# 3_6_1--esp32_-_0105.net
KiCad netlist of a schematic drawn in EasyEDA Pro
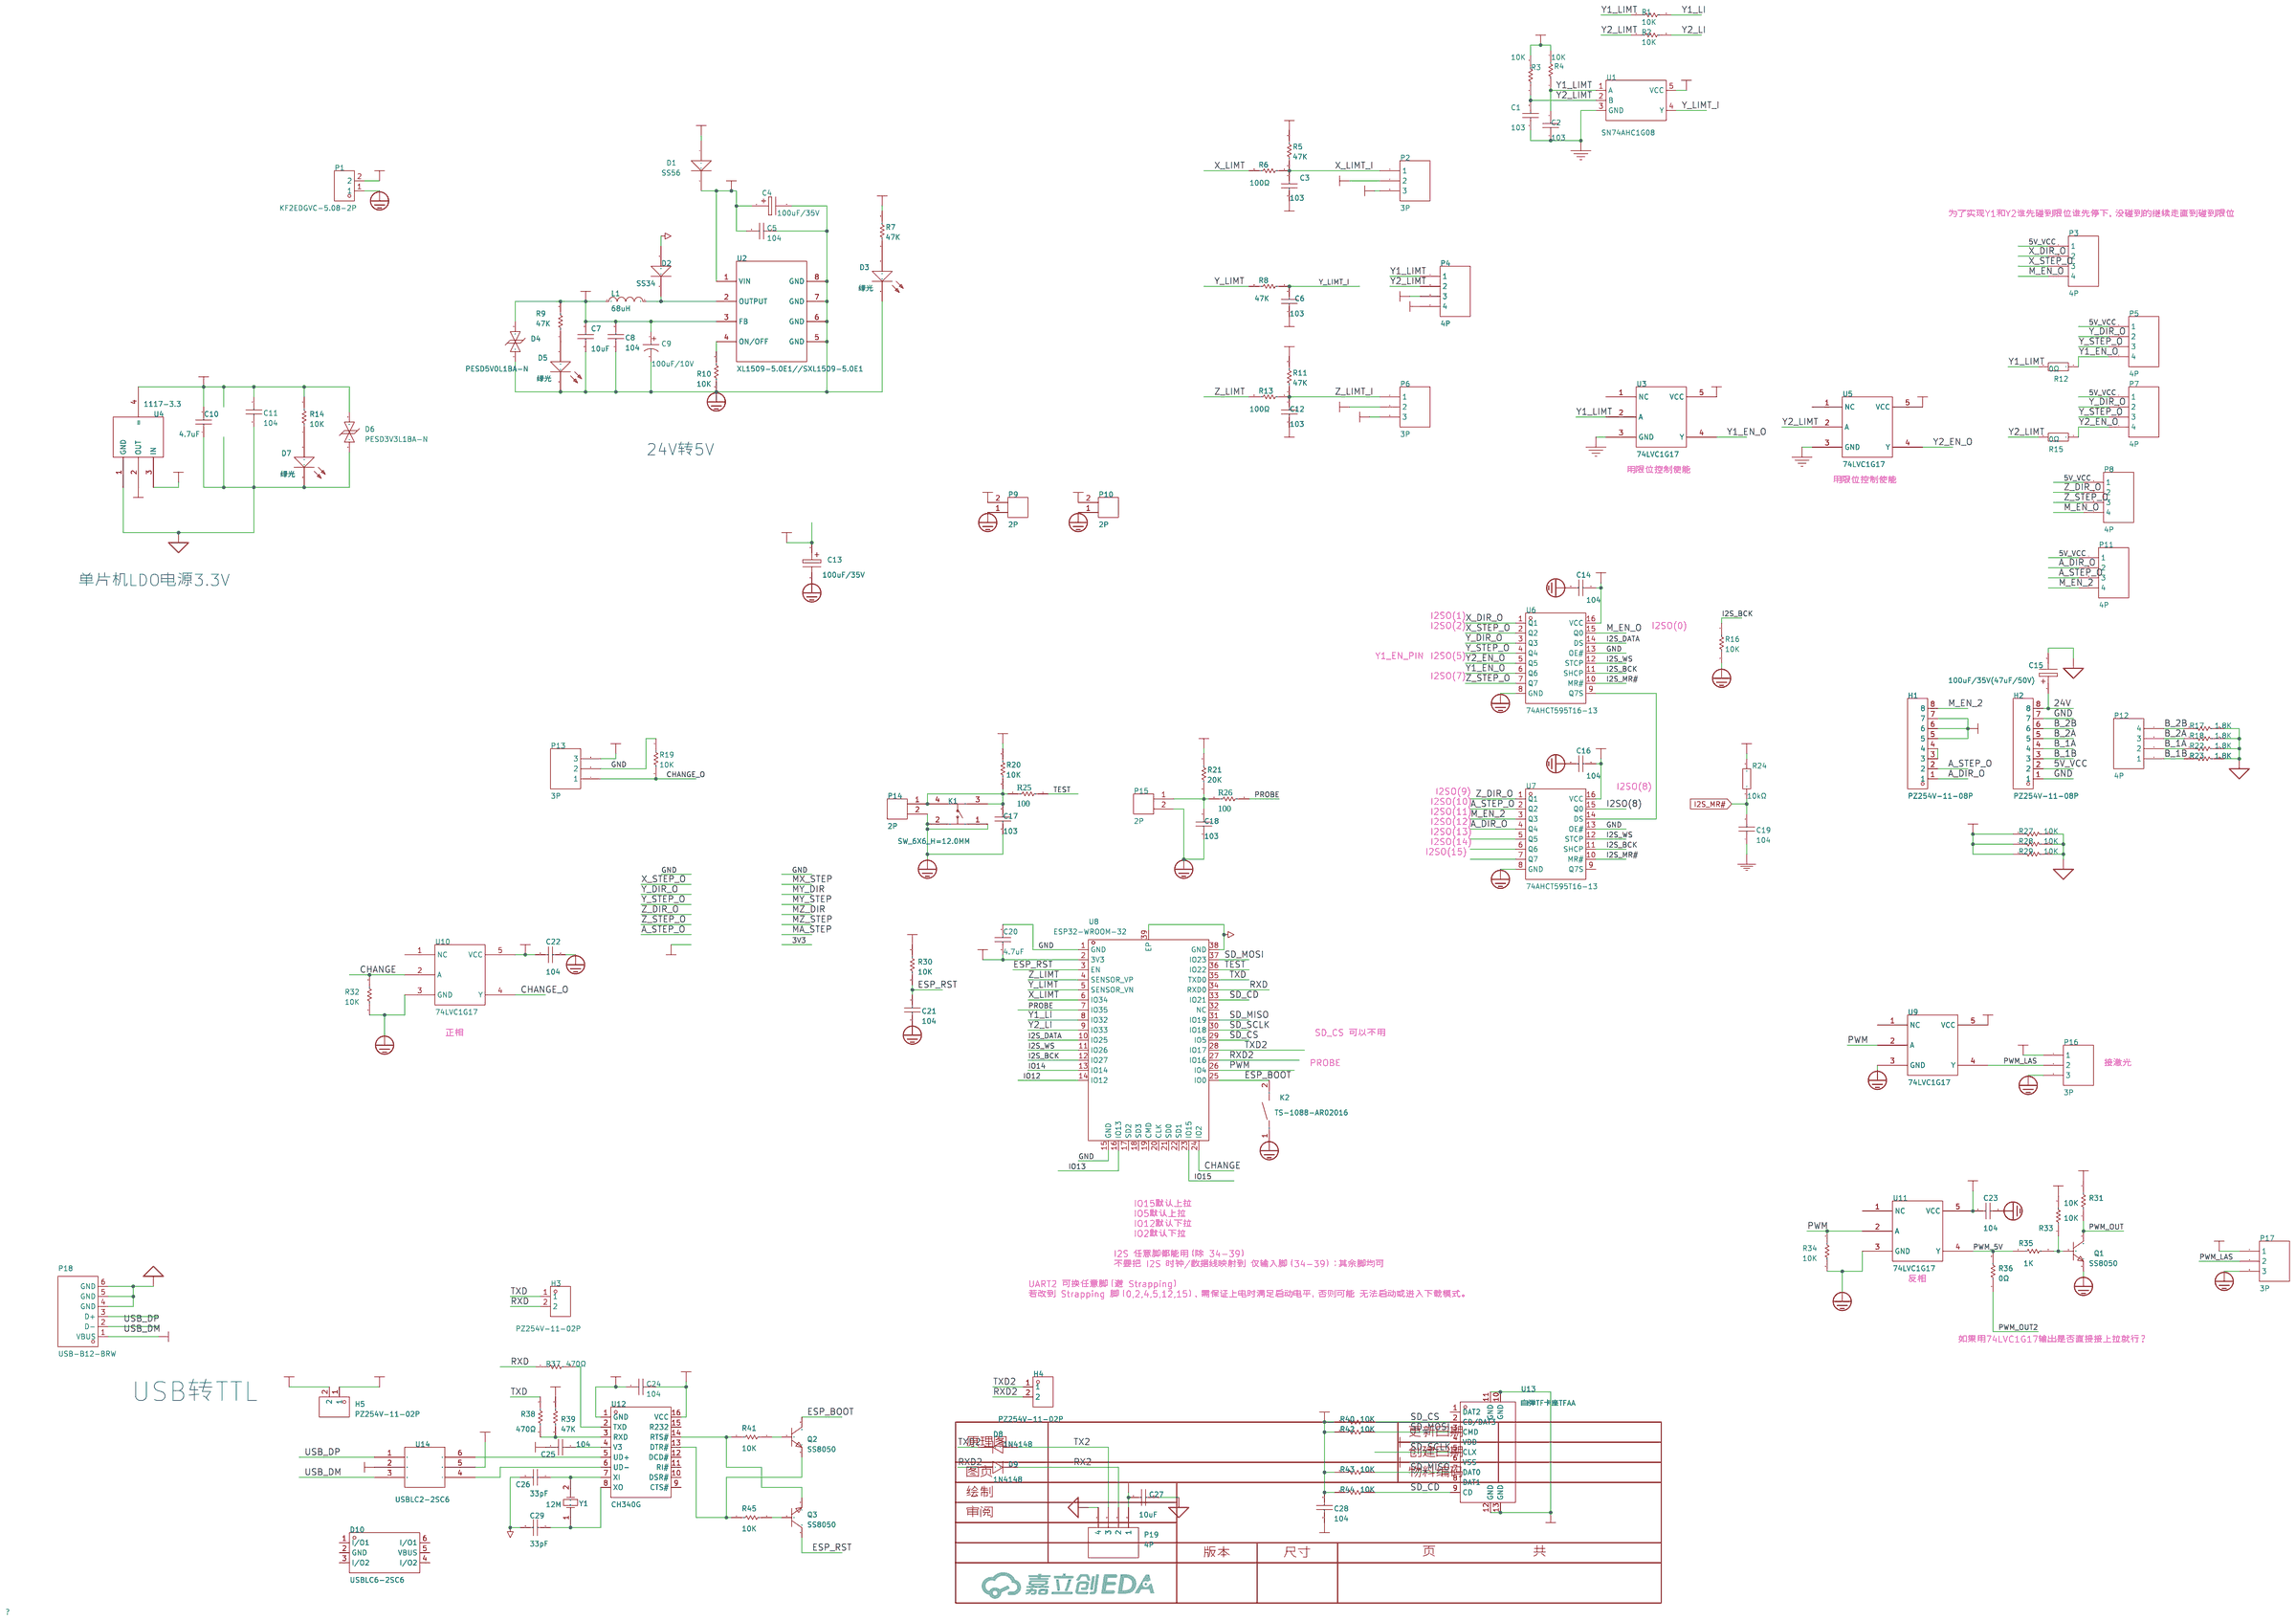
[diagram p0: schematic sheet]

(export (version "E")
  (design (tool "Eeschema 10.0.6"))
  (components
    (comp (ref "C1") (value "103") (footprint "easyedapro:11") (libsource (lib "") (part "CAP_1")))
    (comp (ref "C2") (value "103") (footprint "easyedapro:11") (libsource (lib "") (part "CAP_1")))
    (comp (ref "C3") (value "103") (footprint "easyedapro:11") (libsource (lib "") (part "CAP_1")))
    (comp (ref "C4")
      (value "100uF/35V")
      (footprint "easyedapro:电解电容贴片10x10")
      (libsource (lib "easyedapro") (part "ELECTRO1"))
    )
    (comp (ref "C5")
      (value "104")
      (footprint "easyedapro:0603C")
      (description "Capacitor (Semiconductor SIM Model)")
      (libsource (lib "easyedapro") (part "Cap Semi"))
    )
    (comp (ref "C6") (value "103") (footprint "easyedapro:11") (libsource (lib "") (part "CAP_1")))
    (comp (ref "C7") (value "10uF") (libsource (lib "easyedapro") (part "CAP")))
    (comp (ref "C8")
      (value "104")
      (footprint "easyedapro:0603C")
      (description "Capacitor (Semiconductor SIM Model)")
      (libsource (lib "easyedapro") (part "Cap Semi"))
    )
    (comp (ref "C9")
      (value "100uF/10V")
      (footprint "easyedapro:CAP-SMD_BD5.0-L5.3-W5.3-RD")
      (fields (field (name "Manufacturer Part") "CS1A101M-CRD54") (field (name "Manufacturer") "ST(先科)"))
      (libsource (lib "easyedapro") (part "CS1A101M-CRD54"))
    )
    (comp (ref "C10") (value "4.7uF") (libsource (lib "easyedapro") (part "CAP")))
    (comp (ref "C11")
      (value "104")
      (footprint "easyedapro:0603C")
      (description "Capacitor (Semiconductor SIM Model)")
      (libsource (lib "easyedapro") (part "Cap Semi"))
    )
    (comp (ref "C12") (value "103") (footprint "easyedapro:11") (libsource (lib "") (part "CAP_1")))
    (comp (ref "C13")
      (value "100uF/35V")
      (footprint "easyedapro:电解电容贴片10x10")
      (libsource (lib "easyedapro") (part "ELECTRO1"))
    )
    (comp (ref "C14")
      (value "104")
      (footprint "easyedapro:0603C")
      (description "Capacitor (Semiconductor SIM Model)")
      (libsource (lib "easyedapro") (part "Cap Semi"))
    )
    (comp (ref "C15")
      (value "100uF/35V(47uF/50V)")
      (footprint "easyedapro:电解电容贴片10x10")
      (libsource (lib "easyedapro") (part "ELECTRO1"))
    )
    (comp (ref "C16")
      (value "104")
      (footprint "easyedapro:0603C")
      (description "Capacitor (Semiconductor SIM Model)")
      (libsource (lib "easyedapro") (part "Cap Semi"))
    )
    (comp (ref "C17") (value "103") (footprint "easyedapro:11") (libsource (lib "") (part "CAP_1")))
    (comp (ref "C18") (value "103") (footprint "easyedapro:11") (libsource (lib "") (part "CAP_1")))
    (comp (ref "C19")
      (value "104")
      (footprint "easyedapro:0603C")
      (description "Capacitor (Semiconductor SIM Model)")
      (libsource (lib "easyedapro") (part "Cap Semi"))
    )
    (comp (ref "C20") (value "4.7uF") (libsource (lib "easyedapro") (part "CAP")))
    (comp (ref "C21")
      (value "104")
      (footprint "easyedapro:0603C")
      (description "Capacitor (Semiconductor SIM Model)")
      (libsource (lib "easyedapro") (part "Cap Semi"))
    )
    (comp (ref "C22")
      (value "104")
      (footprint "easyedapro:0603C")
      (description "Capacitor (Semiconductor SIM Model)")
      (libsource (lib "easyedapro") (part "Cap Semi"))
    )
    (comp (ref "C23")
      (value "104")
      (footprint "easyedapro:0603C")
      (description "Capacitor (Semiconductor SIM Model)")
      (libsource (lib "easyedapro") (part "Cap Semi"))
    )
    (comp (ref "C24")
      (value "104")
      (footprint "easyedapro:0603C")
      (description "Capacitor (Semiconductor SIM Model)")
      (libsource (lib "easyedapro") (part "Cap Semi"))
    )
    (comp (ref "C25")
      (value "104")
      (footprint "easyedapro:0603C")
      (description "Capacitor (Semiconductor SIM Model)")
      (libsource (lib "easyedapro") (part "Cap Semi"))
    )
    (comp (ref "C26")
      (value "18pF")
      (footprint "easyedapro:0603C")
      (description "Capacitor (Semiconductor SIM Model)")
      (libsource (lib "easyedapro") (part "Cap Semi"))
    )
    (comp (ref "C27") (value "10uF") (libsource (lib "easyedapro") (part "CAP")))
    (comp (ref "C28")
      (value "104")
      (footprint "easyedapro:11")
      (description "Capacitor (Semiconductor SIM Model)")
      (libsource (lib "easyedapro") (part "Cap Semi"))
    )
    (comp (ref "C29")
      (value "18pF")
      (footprint "easyedapro:0603C")
      (description "Capacitor (Semiconductor SIM Model)")
      (libsource (lib "easyedapro") (part "Cap Semi"))
    )
    (comp (ref "D1") (value "SS56") (footprint "easyedapro:SMA") (libsource (lib "") (part "1N4148_1")))
    (comp (ref "D2") (value "SS34") (libsource (lib "easyedapro") (part "1N4148")))
    (comp (ref "D3")
      (value "绿光")
      (footprint "easyedapro:0603LED")
      (libsource (lib "easyedapro") (part "LED"))
    )
    (comp (ref "D4")
      (value "PESD5V0L1BA-N")
      (footprint "easyedapro:SOD-523_L1.2-W0.8-LS1.6-BI")
      (description "极性:Bidirectional;反向关断电压（典型值）:5V (Max);击穿电压（最小值）:6V;箝位电压:15V;峰值脉冲电流（10/1000us）:5A (8/20us);")
      (fields (field (name "Manufacturer") "BORN伯恩半导体"))
      (libsource (lib "easyedapro") (part "PESD5V0S1BBN"))
    )
    (comp (ref "D5")
      (value "绿光")
      (footprint "easyedapro:0603LED")
      (libsource (lib "easyedapro") (part "LED"))
    )
    (comp (ref "D6")
      (value "PESD3V3L1BA-N")
      (footprint "easyedapro:SOD-523_L1.2-W0.8-LS1.6-BI")
      (description "极性:Bidirectional;反向关断电压（典型值）:5V (Max);击穿电压（最小值）:6V;箝位电压:15V;峰值脉冲电流（10/1000us）:5A (8/20us);")
      (fields (field (name "Manufacturer") "BORN伯恩半导体"))
      (libsource (lib "easyedapro") (part "PESD5V0S1BBN"))
    )
    (comp (ref "D7")
      (value "绿光")
      (footprint "easyedapro:0603LED")
      (libsource (lib "easyedapro") (part "LED"))
    )
    (comp (ref "D8")
      (value "1N4148")
      (footprint "easyedapro:SOD-123_L2.8-W1.8-LS3.7-RD")
      (fields (field (name "Manufacturer") "MCC(美微科)"))
      (libsource (lib "easyedapro") (part "1N4148W-TP"))
    )
    (comp (ref "D9")
      (value "1N4148")
      (footprint "easyedapro:SOD-123_L2.8-W1.8-LS3.7-RD")
      (fields (field (name "Manufacturer") "MCC(美微科)"))
      (libsource (lib "easyedapro") (part "1N4148W-TP"))
    )
    (comp (ref "D10")
      (value "USBLC6-2SC6")
      (footprint "easyedapro:SOT-23-6_L2.9-W1.6-P0.95-LS2.8-BL")
      (description "最大钳位电压:15V;击穿电压:6V;")
      (fields (field (name "Manufacturer") "UMW(友台半导体)"))
      (libsource (lib "easyedapro") (part "USBLC6-2SC6_C2687116"))
    )
    (comp (ref "H1")
      (value "PZ254V-11-08P")
      (footprint "easyedapro:HDR-TH_8P-P2.54-V-M")
      (fields (field (name "Manufacturer") "XFCN(兴飞)"))
      (libsource (lib "easyedapro") (part "PZ254V-11-08P"))
    )
    (comp (ref "H2")
      (value "PZ254V-11-08P")
      (footprint "easyedapro:HDR-TH_8P-P2.54-V-M")
      (fields (field (name "Manufacturer") "XFCN(兴飞)"))
      (libsource (lib "easyedapro") (part "PZ254V-11-08P"))
    )
    (comp (ref "H3")
      (value "PZ254V-11-02P")
      (footprint "easyedapro:HDR-TH_2P-P2.54-V-M")
      (fields (field (name "Manufacturer") "XFCN(兴飞)"))
      (libsource (lib "easyedapro") (part "PZ254V-11-02P"))
    )
    (comp (ref "H4")
      (value "PZ254V-11-02P")
      (footprint "easyedapro:HDR-TH_2P-P2.54-V-M")
      (fields (field (name "Manufacturer") "XFCN(兴飞)"))
      (libsource (lib "easyedapro") (part "PZ254V-11-02P"))
    )
    (comp (ref "H5")
      (value "PZ254V-11-02P")
      (footprint "easyedapro:HDR-TH_2P-P2.54-V-M")
      (fields (field (name "Manufacturer") "XFCN(兴飞)"))
      (libsource (lib "easyedapro") (part "PZ254V-11-02P"))
    )
    (comp (ref "K1")
      (value "SW_6X6_H=12.0MM")
      (footprint "easyedapro:KEY-SMD_4P-L6.0-W6.0-P4.50-LS9.0")
      (libsource (lib "easyedapro") (part "SW_6X6_H=12.0MM"))
    )
    (comp (ref "K2")
      (value "TS-1088-AR02016")
      (footprint "easyedapro:SW-SMD_L3.9-W3.0-P4.45")
      (fields (field (name "Manufacturer") "XUNPU(讯普)"))
      (libsource (lib "easyedapro") (part "TS-1088-AR02016"))
    )
    (comp (ref "L1")
      (value "68uH")
      (footprint "easyedapro:IND-SMD_L7.0-W7.0_SMDRI74-330MT")
      (description "电感值:33uH;精度:±20%;额定电流:960mA;饱和电流(Isat):1.8A;类型:屏蔽电感;")
      (fields (field (name "Manufacturer Part") "SMDRI74-330MT") (field (name "Manufacturer") "SXN(顺翔诺)"))
      (libsource (lib "easyedapro") (part "SMDRI74-330MT"))
    )
    (comp (ref "P1")
      (value "KF2EDGVC-5.08-2P")
      (footprint "easyedapro:CONN-TH_P5.08_KF2EDGVC-5.08-2P")
      (description "连接器类型:板端/插座-闭口;结构:1x2P;间距:5.08mm;颜色:绿色;安装方式:直针;排数:1;每排PIN数:2;额定电流:15A;额定电压:300V;工作温度:-40°C~+105°C;")
      (fields (field (name "Manufacturer") "KEFA(科发)"))
      (libsource (lib "easyedapro") (part "KF2EDGVC-5.08-2P"))
    )
    (comp (ref "P2")
      (value "3P")
      (footprint "easyedapro:HDR1X3_CON")
      (libsource (lib "easyedapro") (part "3P"))
    )
    (comp (ref "P3")
      (value "4P")
      (footprint "easyedapro:HDR1X4_CON")
      (libsource (lib "easyedapro") (part "4P"))
    )
    (comp (ref "P4")
      (value "4P")
      (footprint "easyedapro:HDR1X4_CON")
      (libsource (lib "easyedapro") (part "4P"))
    )
    (comp (ref "P5")
      (value "4P")
      (footprint "easyedapro:HDR1X4_CON")
      (libsource (lib "easyedapro") (part "4P"))
    )
    (comp (ref "P6")
      (value "3P")
      (footprint "easyedapro:HDR1X3_CON")
      (libsource (lib "easyedapro") (part "3P"))
    )
    (comp (ref "P7")
      (value "4P")
      (footprint "easyedapro:HDR1X4_CON")
      (libsource (lib "easyedapro") (part "4P"))
    )
    (comp (ref "P8")
      (value "4P")
      (footprint "easyedapro:HDR1X4_CON")
      (libsource (lib "easyedapro") (part "4P"))
    )
    (comp (ref "P9") (value "2P") (libsource (lib "easyedapro") (part "2P")))
    (comp (ref "P10") (value "2P") (libsource (lib "easyedapro") (part "2P")))
    (comp (ref "P11")
      (value "4P")
      (footprint "easyedapro:HDR1X4_CON")
      (libsource (lib "easyedapro") (part "4P"))
    )
    (comp (ref "P12")
      (value "4P")
      (footprint "easyedapro:HDR1X4_CON")
      (libsource (lib "easyedapro") (part "4P"))
    )
    (comp (ref "P13")
      (value "3P")
      (footprint "easyedapro:HDR1X3_CON")
      (libsource (lib "easyedapro") (part "3P"))
    )
    (comp (ref "P14") (value "2P") (libsource (lib "easyedapro") (part "2P")))
    (comp (ref "P15") (value "2P") (libsource (lib "easyedapro") (part "2P")))
    (comp (ref "P16")
      (value "3P")
      (footprint "easyedapro:HDR1X3_CON")
      (libsource (lib "easyedapro") (part "3P"))
    )
    (comp (ref "P17")
      (value "3P")
      (footprint "easyedapro:HDR1X3_CON")
      (libsource (lib "easyedapro") (part "3P"))
    )
    (comp (ref "P18")
      (value "USB-B12-BRW")
      (footprint "easyedapro:USB-B-TH_USB-B12-BRW")
      (description "连接器类型:Type-B;协议标准:USB 2.0;公母:母;安装方式:直插;触点数量:4P;端口数量:1;额定电流 - 电源:1.5A;工作温度:-20°C~+70°C;")
      (fields (field (name "Manufacturer") "XUNPU(讯普)"))
      (libsource (lib "easyedapro") (part "USB-B12-BRW"))
    )
    (comp (ref "P19")
      (value "4P")
      (footprint "easyedapro:HDR1X4_CON")
      (libsource (lib "easyedapro") (part "4P"))
    )
    (comp (ref "Q1")
      (value "SS8050")
      (footprint "easyedapro:SOT-23-3_L2.9-W1.3-P1.90-LS2.4-BR")
      (fields (field (name "Manufacturer") "CJ（江苏长电/长晶）"))
      (libsource (lib "easyedapro") (part "SS8050_C2150"))
    )
    (comp (ref "Q2")
      (value "SS8050")
      (footprint "easyedapro:SOT-23-3_L2.9-W1.3-P1.90-LS2.4-BR")
      (fields (field (name "Manufacturer") "Doeshare(德芯)"))
      (libsource (lib "easyedapro") (part "SS8050_C2931717"))
    )
    (comp (ref "Q3")
      (value "SS8050")
      (footprint "easyedapro:SOT-23-3_L2.9-W1.3-P1.90-LS2.4-BR")
      (fields (field (name "Manufacturer") "Doeshare(德芯)"))
      (libsource (lib "easyedapro") (part "SS8050_C2931717"))
    )
    (comp (ref "R1")
      (value "10K")
      (footprint "easyedapro:0603R")
      (description "Resistor")
      (libsource (lib "easyedapro") (part "RES"))
    )
    (comp (ref "R2")
      (value "10K")
      (footprint "easyedapro:0603R")
      (description "Resistor")
      (libsource (lib "easyedapro") (part "RES"))
    )
    (comp (ref "R3")
      (value "10K")
      (footprint "easyedapro:0603R")
      (description "Resistor")
      (libsource (lib "easyedapro") (part "RES"))
    )
    (comp (ref "R4")
      (value "10K")
      (footprint "easyedapro:0603R")
      (description "Resistor")
      (libsource (lib "easyedapro") (part "RES"))
    )
    (comp (ref "R5")
      (value "47K")
      (footprint "easyedapro:10")
      (description "Resistor")
      (libsource (lib "easyedapro") (part "RES"))
    )
    (comp (ref "R6")
      (value "100Ω")
      (footprint "easyedapro:10")
      (description "Resistor")
      (libsource (lib "easyedapro") (part "RES"))
    )
    (comp (ref "R7")
      (value "47K")
      (footprint "easyedapro:0603R")
      (description "Resistor")
      (libsource (lib "easyedapro") (part "RES"))
    )
    (comp (ref "R8")
      (value "47K")
      (footprint "easyedapro:10")
      (description "Resistor")
      (libsource (lib "easyedapro") (part "RES"))
    )
    (comp (ref "R9")
      (value "10K")
      (footprint "easyedapro:0603R")
      (description "Resistor")
      (libsource (lib "easyedapro") (part "RES"))
    )
    (comp (ref "R10")
      (value "10K")
      (footprint "easyedapro:0603R")
      (description "Resistor")
      (libsource (lib "easyedapro") (part "RES"))
    )
    (comp (ref "R11")
      (value "47K")
      (footprint "easyedapro:10")
      (description "Resistor")
      (libsource (lib "easyedapro") (part "RES"))
    )
    (comp (ref "R12")
      (value "0Ω")
      (footprint "easyedapro:R0603")
      (description "电阻类型:薄膜电阻;阻值:10kΩ;精度:±0.1%;功率:100mW;温度系数:±25ppm/;最大工作电压:75V;工作温度范围:-55~+155;")
      (fields
        (field (name "Manufacturer Part") "RT0603BRD0710KL")
        (field (name "Manufacturer") "YAGEO(----)")
      )
      (libsource (lib "easyedapro") (part "RT0603BRD0710KL"))
    )
    (comp (ref "R13")
      (value "100Ω")
      (footprint "easyedapro:10")
      (description "Resistor")
      (libsource (lib "easyedapro") (part "RES"))
    )
    (comp (ref "R14")
      (value "10K")
      (footprint "easyedapro:0603R")
      (description "Resistor")
      (libsource (lib "easyedapro") (part "RES"))
    )
    (comp (ref "R15")
      (value "0Ω")
      (footprint "easyedapro:R0603")
      (description "电阻类型:薄膜电阻;阻值:10kΩ;精度:±0.1%;功率:100mW;温度系数:±25ppm/;最大工作电压:75V;工作温度范围:-55~+155;")
      (fields
        (field (name "Manufacturer Part") "RT0603BRD0710KL")
        (field (name "Manufacturer") "YAGEO(----)")
      )
      (libsource (lib "easyedapro") (part "RT0603BRD0710KL"))
    )
    (comp (ref "R16")
      (value "10K")
      (footprint "easyedapro:0603R")
      (description "Resistor")
      (libsource (lib "easyedapro") (part "RES"))
    )
    (comp (ref "R17")
      (value "10K")
      (footprint "easyedapro:0603R")
      (description "Resistor")
      (libsource (lib "easyedapro") (part "10K"))
    )
    (comp (ref "R18")
      (value "10K")
      (footprint "easyedapro:0603R")
      (description "Resistor")
      (libsource (lib "easyedapro") (part "10K"))
    )
    (comp (ref "R19")
      (value "10K")
      (footprint "easyedapro:0603R")
      (description "Resistor")
      (libsource (lib "easyedapro") (part "RES"))
    )
    (comp (ref "R20")
      (value "10K")
      (footprint "easyedapro:0603R")
      (description "Resistor")
      (libsource (lib "easyedapro") (part "RES"))
    )
    (comp (ref "R21")
      (value "10K")
      (footprint "easyedapro:0603R")
      (description "Resistor")
      (libsource (lib "easyedapro") (part "RES"))
    )
    (comp (ref "R22")
      (value "10K")
      (footprint "easyedapro:0603R")
      (description "Resistor")
      (libsource (lib "easyedapro") (part "10K"))
    )
    (comp (ref "R23")
      (value "10K")
      (footprint "easyedapro:0603R")
      (description "Resistor")
      (libsource (lib "easyedapro") (part "10K"))
    )
    (comp (ref "R24")
      (value "10kΩ")
      (footprint "easyedapro:R0603")
      (fields (field (name "Manufacturer Part") "0603WAF1002T5E") (field (name "Manufacturer") "UniOhm"))
      (libsource (lib "easyedapro") (part "10kΩ"))
    )
    (comp (ref "R25")
      (value "100")
      (description "Resistor")
      (fields (field (name "Publisher") "Altium Limited"))
      (libsource (lib "") (part "RES_1"))
    )
    (comp (ref "R26")
      (value "100")
      (description "Resistor")
      (fields (field (name "Publisher") "Altium Limited"))
      (libsource (lib "") (part "RES_1"))
    )
    (comp (ref "R27")
      (value "10K")
      (footprint "easyedapro:0603R")
      (description "Resistor")
      (libsource (lib "easyedapro") (part "10K"))
    )
    (comp (ref "R28")
      (value "10K")
      (footprint "easyedapro:0603R")
      (description "Resistor")
      (libsource (lib "easyedapro") (part "10K"))
    )
    (comp (ref "R29")
      (value "10K")
      (footprint "easyedapro:0603R")
      (description "Resistor")
      (libsource (lib "easyedapro") (part "10K"))
    )
    (comp (ref "R30")
      (value "10K")
      (footprint "easyedapro:0603R")
      (description "Resistor")
      (libsource (lib "easyedapro") (part "RES"))
    )
    (comp (ref "R31")
      (value "10K")
      (description "Resistor")
      (fields (field (name "Publisher") "Altium Limited"))
      (libsource (lib "") (part "RES_1"))
    )
    (comp (ref "R32")
      (value "10K")
      (description "Resistor")
      (fields (field (name "Publisher") "Altium Limited"))
      (libsource (lib "") (part "RES_1"))
    )
    (comp (ref "R33")
      (value "10K")
      (description "Resistor")
      (fields (field (name "Publisher") "Altium Limited"))
      (libsource (lib "") (part "RES_1"))
    )
    (comp (ref "R34")
      (value "10K")
      (description "Resistor")
      (fields (field (name "Publisher") "Altium Limited"))
      (libsource (lib "") (part "RES_1"))
    )
    (comp (ref "R35")
      (value "1K")
      (description "Resistor")
      (fields (field (name "Publisher") "Altium Limited"))
      (libsource (lib "") (part "RES_1"))
    )
    (comp (ref "R36")
      (value "0Ω")
      (description "Resistor")
      (fields (field (name "Publisher") "Altium Limited"))
      (libsource (lib "") (part "RES_1"))
    )
    (comp (ref "R37")
      (value "470Ω")
      (description "Resistor")
      (fields (field (name "Publisher") "Altium Limited"))
      (libsource (lib "") (part "RES_1"))
    )
    (comp (ref "R38")
      (value "470Ω")
      (description "Resistor")
      (fields (field (name "Publisher") "Altium Limited"))
      (libsource (lib "") (part "RES_1"))
    )
    (comp (ref "R39")
      (value "10K")
      (footprint "easyedapro:0603R")
      (description "Resistor")
      (libsource (lib "easyedapro") (part "RES"))
    )
    (comp (ref "R40")
      (value "10K")
      (footprint "easyedapro:10")
      (description "Resistor")
      (libsource (lib "easyedapro") (part "RES"))
    )
    (comp (ref "R41")
      (value "10K")
      (footprint "easyedapro:0603R")
      (description "Resistor")
      (libsource (lib "easyedapro") (part "RES"))
    )
    (comp (ref "R42")
      (value "10K")
      (footprint "easyedapro:10")
      (description "Resistor")
      (libsource (lib "easyedapro") (part "RES"))
    )
    (comp (ref "R43")
      (value "10K")
      (footprint "easyedapro:10")
      (description "Resistor")
      (libsource (lib "easyedapro") (part "RES"))
    )
    (comp (ref "R44")
      (value "10K")
      (footprint "easyedapro:10")
      (description "Resistor")
      (libsource (lib "easyedapro") (part "RES"))
    )
    (comp (ref "R45")
      (value "10K")
      (footprint "easyedapro:0603R")
      (description "Resistor")
      (libsource (lib "easyedapro") (part "RES"))
    )
    (comp (ref "U1")
      (value "SN74AHC1G08")
      (footprint "easyedapro:SC-70-5_L2.1-W1.3-P0.65-LS2.1-BR")
      (description "逻辑类型:与门;通道数:1;工作电压:2V~5.5V;静态电流(Iq):1uA;传播延迟(tpd):7.9ns@5V,50pF;")
      (fields (field (name "Manufacturer") "TI(德州仪器)"))
      (libsource (lib "easyedapro") (part "SN74AHC1G08DCKR"))
    )
    (comp (ref "U2")
      (value "XL1509-5.0E1//SXL1509-5.0E1")
      (footprint "easyedapro:SOIC-8_L5.0-W4.0-P1.27-LS6.0-BL")
      (description "功能类型:降压型;同步整流:-;输出通道数:-;拓扑结构:-;输入电压:-;输出电流(最大值):-;开关频率:-;")
      (fields (field (name "Manufacturer") "XLSEMI(芯龙)"))
      (libsource (lib "easyedapro") (part "XL1509-5.0E1"))
    )
    (comp (ref "U3")
      (value "74LVC1G17")
      (footprint "easyedapro:SMD8")
      (libsource (lib "easyedapro") (part "74LVC1G04"))
    )
    (comp (ref "U4")
      (value "1117-3.3")
      (footprint "easyedapro:SOT-223")
      (libsource (lib "easyedapro") (part "LM1117"))
    )
    (comp (ref "U5")
      (value "74LVC1G17")
      (footprint "easyedapro:SMD8")
      (libsource (lib "easyedapro") (part "74LVC1G04"))
    )
    (comp (ref "U6")
      (value "74AHCT595T16-13")
      (footprint "easyedapro:TSSOP-16_L5.0-W4.4-P0.65-LS6.4-BL")
      (description "功能:串行至串行或并行;工作电压:4.5V~5.5V;元件数:1;每个元件位数:8;")
      (fields (field (name "Manufacturer") "DIODES(美台)"))
      (libsource (lib "easyedapro") (part "74AHCT595T16-13"))
    )
    (comp (ref "U7")
      (value "74AHCT595T16-13")
      (footprint "easyedapro:TSSOP-16_L5.0-W4.4-P0.65-LS6.4-BL")
      (description "功能:串行至串行或并行;工作电压:4.5V~5.5V;元件数:1;每个元件位数:8;")
      (fields (field (name "Manufacturer") "DIODES(美台)"))
      (libsource (lib "easyedapro") (part "74AHCT595T16-13"))
    )
    (comp (ref "U8")
      (value "ESP32-WROOM-32")
      (footprint "easyedapro:WIFIM-SMD_ESP-WROOM-32")
      (description "WiFi+双模蓝牙 双核CPU 网口 顶配MCU 低功耗蓝牙 ESP32系列ESP-WROOM-32模组/ESP-32S 4MB")
      (fields (field (name "Manufacturer") "ESPRESSIF(乐鑫)"))
      (libsource (lib "easyedapro") (part "ESP-WROOM-32"))
    )
    (comp (ref "U9")
      (value "74LVC1G17")
      (footprint "easyedapro:SMD8")
      (libsource (lib "easyedapro") (part "74LVC1G04"))
    )
    (comp (ref "U10")
      (value "74LVC1G17")
      (footprint "easyedapro:SMD8")
      (libsource (lib "easyedapro") (part "74LVC1G04"))
    )
    (comp (ref "U11")
      (value "74LVC1G17")
      (footprint "easyedapro:SMD8")
      (libsource (lib "easyedapro") (part "74LVC1G04"))
    )
    (comp (ref "U12")
      (value "CH340G")
      (footprint "easyedapro:SOIC-16_L9.9-W3.9-P1.27-LS6.0-BL")
      (description "应用功能:收发器;接口协议:USB 2.0;数据速率:2Mbps;")
      (fields (field (name "Manufacturer") "WCH(南京沁恒)"))
      (libsource (lib "easyedapro") (part "CH340G"))
    )
    (comp (ref "U13")
      (value "自弹TF卡座TFAA")
      (footprint "easyedapro:SIM-SMD_C9900015645")
      (libsource (lib "easyedapro") (part "自弹TF卡座TFAA"))
    )
    (comp (ref "U14")
      (value "USBLC2-2SC6")
      (footprint "easyedapro:SOT-23-6")
      (libsource (lib "easyedapro") (part "DIP6"))
    )
    (comp (ref "Y1")
      (value "12M")
      (footprint "easyedapro:晶振贴片49SSMD")
      (description "Crystal Oscillator")
      (libsource (lib "easyedapro") (part "XTAL"))
    )
  )
  (nets
    (net (code "1") (name "/A_DIR_O") (class "Default")
      (node (ref "H1") (pin "1") (pinfunction "1_1") (pintype "unspecified"))
      (node (ref "P11") (pin "2") (pinfunction "2_2") (pintype "unspecified"))
      (node (ref "U7") (pin "4") (pinfunction "Q4_4") (pintype "unspecified"))
    )
    (net (code "2") (name "/A_STEP_O") (class "Default")
      (node (ref "H1") (pin "2") (pinfunction "2_2") (pintype "unspecified"))
      (node (ref "P11") (pin "3") (pinfunction "3_3") (pintype "unspecified"))
      (node (ref "U7") (pin "2") (pinfunction "Q2_2") (pintype "unspecified"))
    )
    (net (code "3") (name "/B_1A") (class "Default")
      (node (ref "H2") (pin "4") (pinfunction "4_4") (pintype "unspecified"))
      (node (ref "P12") (pin "2") (pinfunction "2_2") (pintype "unspecified"))
      (node (ref "R22") (pin "1") (pinfunction "1_1") (pintype "unspecified"))
    )
    (net (code "4") (name "/B_1B") (class "Default")
      (node (ref "H2") (pin "3") (pinfunction "3_3") (pintype "unspecified"))
      (node (ref "P12") (pin "1") (pinfunction "1_1") (pintype "unspecified"))
      (node (ref "R23") (pin "1") (pinfunction "1_1") (pintype "unspecified"))
    )
    (net (code "5") (name "/B_2A") (class "Default")
      (node (ref "H2") (pin "5") (pinfunction "5_5") (pintype "unspecified"))
      (node (ref "P12") (pin "3") (pinfunction "3_3") (pintype "unspecified"))
      (node (ref "R18") (pin "1") (pinfunction "1_1") (pintype "unspecified"))
    )
    (net (code "6") (name "/B_2B") (class "Default")
      (node (ref "H2") (pin "6") (pinfunction "6_6") (pintype "unspecified"))
      (node (ref "P12") (pin "4") (pinfunction "4_4") (pintype "unspecified"))
      (node (ref "R17") (pin "1") (pinfunction "1_1") (pintype "unspecified"))
    )
    (net (code "7") (name "/CHANGE") (class "Default")
      (node (ref "R32") (pin "1") (pinfunction "1_1") (pintype "input"))
      (node (ref "U10") (pin "2") (pinfunction "A_2") (pintype "unspecified"))
      (node (ref "U8") (pin "24") (pinfunction "IO2_24") (pintype "unspecified"))
    )
    (net (code "8") (name "/CHANGE_O") (class "Default")
      (node (ref "P13") (pin "1") (pinfunction "1_1") (pintype "unspecified"))
      (node (ref "R19") (pin "2") (pinfunction "2_2") (pintype "unspecified"))
      (node (ref "U10") (pin "4") (pinfunction "Y_4") (pintype "unspecified"))
    )
    (net (code "9") (name "/ESP_BOOT") (class "Default")
      (node (ref "K2") (pin "2") (pinfunction "2_2") (pintype "unspecified"))
      (node (ref "Q2") (pin "3") (pinfunction "C_3") (pintype "unspecified"))
      (node (ref "U8") (pin "25") (pinfunction "IO0_25") (pintype "unspecified"))
    )
    (net (code "10") (name "/ESP_RST") (class "Default")
      (node (ref "C21") (pin "2") (pinfunction "2_2") (pintype "unspecified"))
      (node (ref "Q3") (pin "3") (pinfunction "C_3") (pintype "unspecified"))
      (node (ref "R30") (pin "2") (pinfunction "2_2") (pintype "unspecified"))
      (node (ref "U8") (pin "3") (pinfunction "EN_3") (pintype "unspecified"))
    )
    (net (code "11") (name "/I2SO(8)") (class "Default")
      (node (ref "U7") (pin "15") (pinfunction "Q0_15") (pintype "unspecified"))
    )
    (net (code "12") (name "/I2S_BCK") (class "Default")
      (node (ref "R16") (pin "1") (pinfunction "1_1") (pintype "unspecified"))
      (node (ref "U6") (pin "11") (pinfunction "SHCP_11") (pintype "unspecified"))
      (node (ref "U7") (pin "11") (pinfunction "SHCP_11") (pintype "unspecified"))
      (node (ref "U8") (pin "12") (pinfunction "IO27_12") (pintype "unspecified"))
    )
    (net (code "13") (name "/I2S_DATA") (class "Default")
      (node (ref "U6") (pin "14") (pinfunction "DS_14") (pintype "unspecified"))
      (node (ref "U8") (pin "10") (pinfunction "IO25_10") (pintype "unspecified"))
    )
    (net (code "14") (name "/I2S_WS") (class "Default")
      (node (ref "U6") (pin "12") (pinfunction "STCP_12") (pintype "unspecified"))
      (node (ref "U7") (pin "12") (pinfunction "STCP_12") (pintype "unspecified"))
      (node (ref "U8") (pin "11") (pinfunction "IO26_11") (pintype "unspecified"))
    )
    (net (code "15") (name "/IO12") (class "Default")
      (node (ref "U8") (pin "14") (pinfunction "IO12_14") (pintype "unspecified"))
    )
    (net (code "16") (name "/IO13") (class "Default")
      (node (ref "U8") (pin "16") (pinfunction "IO13_16") (pintype "unspecified"))
    )
    (net (code "17") (name "/IO14") (class "Default")
      (node (ref "U8") (pin "13") (pinfunction "IO14_13") (pintype "unspecified"))
    )
    (net (code "18") (name "/IO15") (class "Default")
      (node (ref "U8") (pin "23") (pinfunction "IO15_23") (pintype "unspecified"))
    )
    (net (code "25") (name "/M_EN_2") (class "Default")
      (node (ref "H1") (pin "8") (pinfunction "8_8") (pintype "unspecified"))
      (node (ref "P11") (pin "4") (pinfunction "4_4") (pintype "unspecified"))
      (node (ref "U7") (pin "3") (pinfunction "Q3_3") (pintype "unspecified"))
    )
    (net (code "26") (name "/M_EN_O") (class "Default")
      (node (ref "P3") (pin "4") (pinfunction "4_4") (pintype "unspecified"))
      (node (ref "P8") (pin "4") (pinfunction "4_4") (pintype "unspecified"))
      (node (ref "U6") (pin "15") (pinfunction "Q0_15") (pintype "unspecified"))
    )
    (net (code "27") (name "/PROBE") (class "Default")
      (node (ref "R26") (pin "1") (pinfunction "1_1") (pintype "input"))
      (node (ref "U8") (pin "7") (pinfunction "IO35_7") (pintype "unspecified"))
    )
    (net (code "28") (name "/PWM") (class "Default")
      (node (ref "R34") (pin "1") (pinfunction "1_1") (pintype "input"))
      (node (ref "U11") (pin "2") (pinfunction "A_2") (pintype "unspecified"))
      (node (ref "U8") (pin "26") (pinfunction "IO4_26") (pintype "unspecified"))
      (node (ref "U9") (pin "2") (pinfunction "A_2") (pintype "unspecified"))
    )
    (net (code "29") (name "/PWM_5V") (class "Default")
      (node (ref "R35") (pin "1") (pinfunction "1_1") (pintype "input"))
      (node (ref "R36") (pin "2") (pinfunction "2_2") (pintype "input"))
      (node (ref "U11") (pin "4") (pinfunction "Y_4") (pintype "unspecified"))
    )
    (net (code "30") (name "/PWM_LAS") (class "Default")
      (node (ref "P16") (pin "2") (pinfunction "2_2") (pintype "unspecified"))
      (node (ref "P17") (pin "2") (pinfunction "2_2") (pintype "unspecified"))
      (node (ref "U9") (pin "4") (pinfunction "Y_4") (pintype "unspecified"))
    )
    (net (code "31") (name "/PWM_OUT") (class "Default")
      (node (ref "Q1") (pin "3") (pinfunction "C_3") (pintype "input"))
      (node (ref "R31") (pin "1") (pinfunction "1_1") (pintype "input"))
    )
    (net (code "32") (name "/PWM_OUT2") (class "Default")
      (node (ref "R36") (pin "1") (pinfunction "1_1") (pintype "input"))
    )
    (net (code "33") (name "/RX2") (class "Default")
      (node (ref "D9") (pin "1") (pinfunction "c_1") (pintype "input"))
      (node (ref "P19") (pin "2") (pinfunction "2_2") (pintype "unspecified"))
    )
    (net (code "34") (name "/RXD") (class "Default")
      (node (ref "H3") (pin "2") (pinfunction "2_2") (pintype "unspecified"))
      (node (ref "R37") (pin "1") (pinfunction "1_1") (pintype "input"))
      (node (ref "U8") (pin "34") (pinfunction "RXD0_34") (pintype "unspecified"))
    )
    (net (code "35") (name "/RXD2") (class "Default")
      (node (ref "D9") (pin "2") (pinfunction "A_2") (pintype "input"))
      (node (ref "H4") (pin "2") (pinfunction "2_2") (pintype "unspecified"))
      (node (ref "U8") (pin "27") (pinfunction "IO16_27") (pintype "unspecified"))
    )
    (net (code "36") (name "/SD_CD") (class "Default")
      (node (ref "R44") (pin "1") (pinfunction "1_1") (pintype "unspecified"))
      (node (ref "U13") (pin "9") (pinfunction "CD_9") (pintype "unspecified"))
      (node (ref "U8") (pin "33") (pinfunction "IO21_33") (pintype "unspecified"))
    )
    (net (code "37") (name "/SD_CS") (class "Default")
      (node (ref "R40") (pin "1") (pinfunction "1_1") (pintype "unspecified"))
      (node (ref "U13") (pin "2") (pinfunction "CD/DAT3_2") (pintype "unspecified"))
      (node (ref "U8") (pin "29") (pinfunction "IO5_29") (pintype "unspecified"))
    )
    (net (code "38") (name "/SD_MISO") (class "Default")
      (node (ref "R43") (pin "1") (pinfunction "1_1") (pintype "unspecified"))
      (node (ref "U13") (pin "7") (pinfunction "DAT0_7") (pintype "unspecified"))
      (node (ref "U8") (pin "31") (pinfunction "IO19_31") (pintype "unspecified"))
    )
    (net (code "39") (name "/SD_MOSI") (class "Default")
      (node (ref "R42") (pin "1") (pinfunction "1_1") (pintype "unspecified"))
      (node (ref "U13") (pin "3") (pinfunction "CMD_3") (pintype "unspecified"))
      (node (ref "U8") (pin "37") (pinfunction "IO23_37") (pintype "unspecified"))
    )
    (net (code "40") (name "/SD_SCLK") (class "Default")
      (node (ref "U13") (pin "5") (pinfunction "CLX_5") (pintype "unspecified"))
      (node (ref "U8") (pin "30") (pinfunction "IO18_30") (pintype "unspecified"))
    )
    (net (code "41") (name "/TEST") (class "Default")
      (node (ref "R25") (pin "1") (pinfunction "1_1") (pintype "input"))
      (node (ref "U8") (pin "36") (pinfunction "IO22_36") (pintype "unspecified"))
    )
    (net (code "42") (name "/TX2") (class "Default")
      (node (ref "D8") (pin "2") (pinfunction "A_2") (pintype "input"))
      (node (ref "P19") (pin "3") (pinfunction "3_3") (pintype "unspecified"))
    )
    (net (code "43") (name "/TXD") (class "Default")
      (node (ref "H3") (pin "1") (pinfunction "1_1") (pintype "unspecified"))
      (node (ref "R38") (pin "1") (pinfunction "1_1") (pintype "input"))
      (node (ref "U8") (pin "35") (pinfunction "TXD0_35") (pintype "unspecified"))
    )
    (net (code "44") (name "/TXD2") (class "Default")
      (node (ref "D8") (pin "1") (pinfunction "c_1") (pintype "input"))
      (node (ref "H4") (pin "1") (pinfunction "1_1") (pintype "unspecified"))
      (node (ref "U8") (pin "28") (pinfunction "IO17_28") (pintype "unspecified"))
    )
    (net (code "45") (name "/USB_DM") (class "Default")
      (node (ref "P18") (pin "2") (pinfunction "D-_2") (pintype "unspecified"))
      (node (ref "U14") (pin "3") (pinfunction "3_3") (pintype "unspecified"))
    )
    (net (code "46") (name "/USB_DP") (class "Default")
      (node (ref "P18") (pin "3") (pinfunction "D+_3") (pintype "unspecified"))
      (node (ref "U14") (pin "1") (pinfunction "1_1") (pintype "unspecified"))
    )
    (net (code "47") (name "/X_DIR_O") (class "Default")
      (node (ref "P3") (pin "2") (pinfunction "2_2") (pintype "unspecified"))
      (node (ref "U6") (pin "1") (pinfunction "Q1_1") (pintype "unspecified"))
    )
    (net (code "48") (name "/X_LIMT") (class "Default")
      (node (ref "R6") (pin "2") (pinfunction "2_2") (pintype "unspecified"))
      (node (ref "U8") (pin "6") (pinfunction "IO34_6") (pintype "unspecified"))
    )
    (net (code "49") (name "/X_LIMT_I") (class "Default")
      (node (ref "C3") (pin "2") (pinfunction "2_2") (pintype "unspecified"))
      (node (ref "P2") (pin "1") (pinfunction "1_1") (pintype "unspecified"))
      (node (ref "R5") (pin "1") (pinfunction "1_1") (pintype "unspecified"))
      (node (ref "R6") (pin "1") (pinfunction "1_1") (pintype "unspecified"))
    )
    (net (code "50") (name "/X_STEP_O") (class "Default")
      (node (ref "P3") (pin "3") (pinfunction "3_3") (pintype "unspecified"))
      (node (ref "U6") (pin "2") (pinfunction "Q2_2") (pintype "unspecified"))
    )
    (net (code "51") (name "/Y1_EN_O") (class "Default")
      (node (ref "P5") (pin "4") (pinfunction "4_4") (pintype "unspecified"))
      (node (ref "R12") (pin "1") (pinfunction "1_1") (pintype "unspecified"))
      (node (ref "U3") (pin "4") (pinfunction "Y_4") (pintype "unspecified"))
      (node (ref "U6") (pin "6") (pinfunction "Q6_6") (pintype "unspecified"))
    )
    (net (code "52") (name "/Y1_LI") (class "Default")
      (node (ref "R1") (pin "2") (pinfunction "2_2") (pintype "unspecified"))
      (node (ref "U8") (pin "8") (pinfunction "IO32_8") (pintype "unspecified"))
    )
    (net (code "53") (name "/Y1_LIMT") (class "Default")
      (node (ref "C2") (pin "2") (pinfunction "2_2") (pintype "unspecified"))
      (node (ref "P4") (pin "1") (pinfunction "1_1") (pintype "unspecified"))
      (node (ref "R1") (pin "1") (pinfunction "1_1") (pintype "unspecified"))
      (node (ref "R12") (pin "2") (pinfunction "2_2") (pintype "unspecified"))
      (node (ref "R4") (pin "2") (pinfunction "2_2") (pintype "unspecified"))
      (node (ref "U1") (pin "1") (pinfunction "A_1") (pintype "unspecified"))
      (node (ref "U3") (pin "2") (pinfunction "A_2") (pintype "unspecified"))
    )
    (net (code "54") (name "/Y2_EN_O") (class "Default")
      (node (ref "P7") (pin "4") (pinfunction "4_4") (pintype "unspecified"))
      (node (ref "R15") (pin "1") (pinfunction "1_1") (pintype "unspecified"))
      (node (ref "U5") (pin "4") (pinfunction "Y_4") (pintype "unspecified"))
      (node (ref "U6") (pin "5") (pinfunction "Q5_5") (pintype "unspecified"))
    )
    (net (code "55") (name "/Y2_LI") (class "Default")
      (node (ref "R2") (pin "2") (pinfunction "2_2") (pintype "unspecified"))
      (node (ref "U8") (pin "9") (pinfunction "IO33_9") (pintype "unspecified"))
    )
    (net (code "56") (name "/Y2_LIMT") (class "Default")
      (node (ref "C1") (pin "2") (pinfunction "2_2") (pintype "unspecified"))
      (node (ref "P4") (pin "2") (pinfunction "2_2") (pintype "unspecified"))
      (node (ref "R15") (pin "2") (pinfunction "2_2") (pintype "unspecified"))
      (node (ref "R2") (pin "1") (pinfunction "1_1") (pintype "unspecified"))
      (node (ref "R3") (pin "2") (pinfunction "2_2") (pintype "unspecified"))
      (node (ref "U1") (pin "2") (pinfunction "B_2") (pintype "unspecified"))
      (node (ref "U5") (pin "2") (pinfunction "A_2") (pintype "unspecified"))
    )
    (net (code "57") (name "/Y_DIR_O") (class "Default")
      (node (ref "P5") (pin "2") (pinfunction "2_2") (pintype "unspecified"))
      (node (ref "P7") (pin "2") (pinfunction "2_2") (pintype "unspecified"))
      (node (ref "U6") (pin "3") (pinfunction "Q3_3") (pintype "unspecified"))
    )
    (net (code "58") (name "/Y_LIMT") (class "Default")
      (node (ref "R8") (pin "2") (pinfunction "2_2") (pintype "unspecified"))
      (node (ref "U8") (pin "5") (pinfunction "SENSOR_VN_5") (pintype "unspecified"))
    )
    (net (code "59") (name "/Y_LIMT_I") (class "Default")
      (node (ref "C6") (pin "2") (pinfunction "2_2") (pintype "unspecified"))
      (node (ref "R8") (pin "1") (pinfunction "1_1") (pintype "unspecified"))
      (node (ref "U1") (pin "4") (pinfunction "Y_4") (pintype "unspecified"))
    )
    (net (code "60") (name "/Y_STEP_O") (class "Default")
      (node (ref "P5") (pin "3") (pinfunction "3_3") (pintype "unspecified"))
      (node (ref "P7") (pin "3") (pinfunction "3_3") (pintype "unspecified"))
      (node (ref "U6") (pin "4") (pinfunction "Q4_4") (pintype "unspecified"))
    )
    (net (code "61") (name "/Z_DIR_O") (class "Default")
      (node (ref "P8") (pin "2") (pinfunction "2_2") (pintype "unspecified"))
      (node (ref "U7") (pin "1") (pinfunction "Q1_1") (pintype "unspecified"))
    )
    (net (code "62") (name "/Z_LIMT") (class "Default")
      (node (ref "R13") (pin "2") (pinfunction "2_2") (pintype "unspecified"))
      (node (ref "U8") (pin "4") (pinfunction "SENSOR_VP_4") (pintype "unspecified"))
    )
    (net (code "63") (name "/Z_LIMT_I") (class "Default")
      (node (ref "C12") (pin "2") (pinfunction "2_2") (pintype "unspecified"))
      (node (ref "P6") (pin "1") (pinfunction "1_1") (pintype "unspecified"))
      (node (ref "R11") (pin "1") (pinfunction "1_1") (pintype "unspecified"))
      (node (ref "R13") (pin "1") (pinfunction "1_1") (pintype "unspecified"))
    )
    (net (code "64") (name "/Z_STEP_O") (class "Default")
      (node (ref "P8") (pin "3") (pinfunction "3_3") (pintype "unspecified"))
      (node (ref "U6") (pin "7") (pinfunction "Q7_7") (pintype "unspecified"))
    )
    (net (code "65") (name "3V3") (class "Default")
      (node (ref "C10") (pin "2") (pinfunction "2_2") (pintype "input"))
      (node (ref "C11") (pin "2") (pinfunction "2_2") (pintype "unspecified"))
      (node (ref "C20") (pin "1") (pinfunction "1_1") (pintype "input"))
      (node (ref "C28") (pin "2") (pinfunction "2_2") (pintype "unspecified"))
      (node (ref "D6") (pin "2") (pinfunction "2_2") (pintype "input"))
      (node (ref "R14") (pin "2") (pinfunction "2_2") (pintype "unspecified"))
      (node (ref "R20") (pin "1") (pinfunction "1_1") (pintype "unspecified"))
      (node (ref "R30") (pin "1") (pinfunction "1_1") (pintype "unspecified"))
      (node (ref "R40") (pin "2") (pinfunction "2_2") (pintype "unspecified"))
      (node (ref "R42") (pin "2") (pinfunction "2_2") (pintype "unspecified"))
      (node (ref "R43") (pin "2") (pinfunction "2_2") (pintype "unspecified"))
      (node (ref "R44") (pin "2") (pinfunction "2_2") (pintype "unspecified"))
      (node (ref "U13") (pin "4") (pinfunction "VDD_4") (pintype "unspecified"))
      (node (ref "U4") (pin "2") (pinfunction "OUT_2") (pintype "unspecified"))
      (node (ref "U4") (pin "4") (pinfunction "=_4") (pintype "unspecified"))
      (node (ref "U8") (pin "2") (pinfunction "3V3_2") (pintype "unspecified"))
    )
    (net (code "66") (name "5V_VCC") (class "Default")
      (node (ref "C14") (pin "1") (pinfunction "1_1") (pintype "unspecified"))
      (node (ref "C16") (pin "1") (pinfunction "1_1") (pintype "unspecified"))
      (node (ref "C22") (pin "2") (pinfunction "2_2") (pintype "unspecified"))
      (node (ref "C23") (pin "2") (pinfunction "2_2") (pintype "unspecified"))
      (node (ref "C24") (pin "1") (pinfunction "1_1") (pintype "unspecified"))
      (node (ref "C27") (pin "1") (pinfunction "1_1") (pintype "input"))
      (node (ref "C7") (pin "1") (pinfunction "1_1") (pintype "input"))
      (node (ref "C8") (pin "2") (pinfunction "2_2") (pintype "unspecified"))
      (node (ref "C9") (pin "1") (pinfunction "1_1") (pintype "input"))
      (node (ref "D4") (pin "2") (pinfunction "2_2") (pintype "input"))
      (node (ref "H1") (pin "5") (pinfunction "5_5") (pintype "unspecified"))
      (node (ref "H1") (pin "6") (pinfunction "6_6") (pintype "unspecified"))
      (node (ref "H1") (pin "7") (pinfunction "7_7") (pintype "unspecified"))
      (node (ref "H2") (pin "2") (pinfunction "2_2") (pintype "unspecified"))
      (node (ref "H5") (pin "1") (pinfunction "1_1") (pintype "unspecified"))
      (node (ref "L1") (pin "1") (pinfunction "1_1") (pintype "unspecified"))
      (node (ref "P11") (pin "1") (pinfunction "1_1") (pintype "unspecified"))
      (node (ref "P13") (pin "3") (pinfunction "3_3") (pintype "unspecified"))
      (node (ref "P17") (pin "1") (pinfunction "1_1") (pintype "unspecified"))
      (node (ref "P19") (pin "1") (pinfunction "1_1") (pintype "unspecified"))
      (node (ref "P2") (pin "3") (pinfunction "3_3") (pintype "unspecified"))
      (node (ref "P3") (pin "1") (pinfunction "1_1") (pintype "unspecified"))
      (node (ref "P4") (pin "4") (pinfunction "4_4") (pintype "unspecified"))
      (node (ref "P5") (pin "1") (pinfunction "1_1") (pintype "unspecified"))
      (node (ref "P6") (pin "3") (pinfunction "3_3") (pintype "unspecified"))
      (node (ref "P7") (pin "1") (pinfunction "1_1") (pintype "unspecified"))
      (node (ref "P8") (pin "1") (pinfunction "1_1") (pintype "unspecified"))
      (node (ref "R11") (pin "2") (pinfunction "2_2") (pintype "unspecified"))
      (node (ref "R21") (pin "1") (pinfunction "1_1") (pintype "unspecified"))
      (node (ref "R24") (pin "2") (pinfunction "2_2") (pintype "input"))
      (node (ref "R27") (pin "1") (pinfunction "1_1") (pintype "unspecified"))
      (node (ref "R28") (pin "1") (pinfunction "1_1") (pintype "unspecified"))
      (node (ref "R29") (pin "1") (pinfunction "1_1") (pintype "unspecified"))
      (node (ref "R3") (pin "1") (pinfunction "1_1") (pintype "unspecified"))
      (node (ref "R31") (pin "2") (pinfunction "2_2") (pintype "input"))
      (node (ref "R33") (pin "2") (pinfunction "2_2") (pintype "input"))
      (node (ref "R39") (pin "2") (pinfunction "2_2") (pintype "unspecified"))
      (node (ref "R4") (pin "1") (pinfunction "1_1") (pintype "unspecified"))
      (node (ref "R5") (pin "2") (pinfunction "2_2") (pintype "unspecified"))
      (node (ref "R9") (pin "2") (pinfunction "2_2") (pintype "unspecified"))
      (node (ref "U1") (pin "5") (pinfunction "VCC_5") (pintype "unspecified"))
      (node (ref "U10") (pin "5") (pinfunction "VCC_5") (pintype "unspecified"))
      (node (ref "U11") (pin "5") (pinfunction "VCC_5") (pintype "unspecified"))
      (node (ref "U12") (pin "16") (pinfunction "VCC_16") (pintype "unspecified"))
      (node (ref "U2") (pin "3") (pinfunction "FB_3") (pintype "input"))
      (node (ref "U3") (pin "5") (pinfunction "VCC_5") (pintype "unspecified"))
      (node (ref "U4") (pin "3") (pinfunction "IN_3") (pintype "unspecified"))
      (node (ref "U5") (pin "5") (pinfunction "VCC_5") (pintype "unspecified"))
      (node (ref "U6") (pin "16") (pinfunction "VCC_16") (pintype "unspecified"))
      (node (ref "U7") (pin "16") (pinfunction "VCC_16") (pintype "unspecified"))
      (node (ref "U9") (pin "5") (pinfunction "VCC_5") (pintype "unspecified"))
    )
    (net (code "67") (name "24V") (class "Default")
      (node (ref "C13") (pin "1") (pintype "unspecified"))
      (node (ref "C15") (pin "1") (pintype "unspecified"))
      (node (ref "D1") (pin "1") (pinfunction "1_1") (pintype "unspecified"))
      (node (ref "H2") (pin "8") (pinfunction "8_8") (pintype "unspecified"))
      (node (ref "P1") (pin "2") (pinfunction "2_2") (pintype "unspecified"))
      (node (ref "P10") (pin "2") (pintype "input"))
      (node (ref "P16") (pin "1") (pinfunction "1_1") (pintype "unspecified"))
      (node (ref "P9") (pin "2") (pintype "input"))
      (node (ref "R7") (pin "2") (pinfunction "2_2") (pintype "unspecified"))
    )
    (net (code "68") (name "GND") (class "Default")
      (node (ref "C1") (pin "1") (pinfunction "1_1") (pintype "unspecified"))
      (node (ref "C10") (pin "1") (pinfunction "1_1") (pintype "input"))
      (node (ref "C11") (pin "1") (pinfunction "1_1") (pintype "unspecified"))
      (node (ref "C12") (pin "1") (pinfunction "1_1") (pintype "unspecified"))
      (node (ref "C13") (pin "2") (pintype "unspecified"))
      (node (ref "C14") (pin "2") (pinfunction "2_2") (pintype "unspecified"))
      (node (ref "C15") (pin "2") (pintype "unspecified"))
      (node (ref "C16") (pin "2") (pinfunction "2_2") (pintype "unspecified"))
      (node (ref "C17") (pin "1") (pinfunction "1_1") (pintype "unspecified"))
      (node (ref "C18") (pin "1") (pinfunction "1_1") (pintype "unspecified"))
      (node (ref "C19") (pin "1") (pinfunction "1_1") (pintype "unspecified"))
      (node (ref "C2") (pin "1") (pinfunction "1_1") (pintype "unspecified"))
      (node (ref "C20") (pin "2") (pinfunction "2_2") (pintype "input"))
      (node (ref "C21") (pin "1") (pinfunction "1_1") (pintype "unspecified"))
      (node (ref "C22") (pin "1") (pinfunction "1_1") (pintype "unspecified"))
      (node (ref "C23") (pin "1") (pinfunction "1_1") (pintype "unspecified"))
      (node (ref "C24") (pin "2") (pinfunction "2_2") (pintype "unspecified"))
      (node (ref "C25") (pin "2") (pinfunction "2_2") (pintype "unspecified"))
      (node (ref "C26") (pin "2") (pinfunction "2_2") (pintype "unspecified"))
      (node (ref "C27") (pin "2") (pinfunction "2_2") (pintype "input"))
      (node (ref "C28") (pin "1") (pinfunction "1_1") (pintype "unspecified"))
      (node (ref "C29") (pin "2") (pinfunction "2_2") (pintype "unspecified"))
      (node (ref "C3") (pin "1") (pinfunction "1_1") (pintype "unspecified"))
      (node (ref "C4") (pin "2") (pintype "unspecified"))
      (node (ref "C5") (pin "1") (pinfunction "1_1") (pintype "unspecified"))
      (node (ref "C6") (pin "1") (pinfunction "1_1") (pintype "unspecified"))
      (node (ref "C7") (pin "2") (pinfunction "2_2") (pintype "input"))
      (node (ref "C8") (pin "1") (pinfunction "1_1") (pintype "unspecified"))
      (node (ref "C9") (pin "2") (pinfunction "2_2") (pintype "input"))
      (node (ref "D2") (pin "1") (pinfunction "1_1") (pintype "input"))
      (node (ref "D3") (pin "2") (pinfunction "2_2") (pintype "unspecified"))
      (node (ref "D4") (pin "1") (pinfunction "1_1") (pintype "input"))
      (node (ref "D5") (pin "2") (pinfunction "2_2") (pintype "unspecified"))
      (node (ref "D6") (pin "1") (pinfunction "1_1") (pintype "input"))
      (node (ref "D7") (pin "2") (pinfunction "2_2") (pintype "unspecified"))
      (node (ref "H2") (pin "1") (pinfunction "1_1") (pintype "unspecified"))
      (node (ref "H2") (pin "7") (pinfunction "7_7") (pintype "unspecified"))
      (node (ref "K1") (pin "1") (pinfunction "1_1") (pintype "unspecified"))
      (node (ref "K1") (pin "2") (pinfunction "2_2") (pintype "unspecified"))
      (node (ref "K2") (pin "1") (pinfunction "1_1") (pintype "unspecified"))
      (node (ref "P1") (pin "1") (pinfunction "1_1") (pintype "unspecified"))
      (node (ref "P10") (pin "1") (pintype "input"))
      (node (ref "P13") (pin "2") (pinfunction "2_2") (pintype "unspecified"))
      (node (ref "P14") (pin "2") (pintype "input"))
      (node (ref "P15") (pin "2") (pintype "input"))
      (node (ref "P16") (pin "3") (pinfunction "3_3") (pintype "unspecified"))
      (node (ref "P17") (pin "3") (pinfunction "3_3") (pintype "unspecified"))
      (node (ref "P18") (pin "4") (pinfunction "GND_4") (pintype "unspecified"))
      (node (ref "P18") (pin "5") (pinfunction "GND_5") (pintype "unspecified"))
      (node (ref "P18") (pin "6") (pinfunction "GND_6") (pintype "unspecified"))
      (node (ref "P19") (pin "4") (pinfunction "4_4") (pintype "unspecified"))
      (node (ref "P2") (pin "2") (pinfunction "2_2") (pintype "unspecified"))
      (node (ref "P4") (pin "3") (pinfunction "3_3") (pintype "unspecified"))
      (node (ref "P6") (pin "2") (pinfunction "2_2") (pintype "unspecified"))
      (node (ref "P9") (pin "1") (pintype "input"))
      (node (ref "Q1") (pin "2") (pinfunction "E_2") (pintype "input"))
      (node (ref "R10") (pin "2") (pinfunction "2_2") (pintype "unspecified"))
      (node (ref "R16") (pin "2") (pinfunction "2_2") (pintype "unspecified"))
      (node (ref "R17") (pin "2") (pinfunction "2_2") (pintype "unspecified"))
      (node (ref "R18") (pin "2") (pinfunction "2_2") (pintype "unspecified"))
      (node (ref "R19") (pin "1") (pinfunction "1_1") (pintype "unspecified"))
      (node (ref "R22") (pin "2") (pinfunction "2_2") (pintype "unspecified"))
      (node (ref "R23") (pin "2") (pinfunction "2_2") (pintype "unspecified"))
      (node (ref "R27") (pin "2") (pinfunction "2_2") (pintype "unspecified"))
      (node (ref "R28") (pin "2") (pinfunction "2_2") (pintype "unspecified"))
      (node (ref "R29") (pin "2") (pinfunction "2_2") (pintype "unspecified"))
      (node (ref "R32") (pin "2") (pinfunction "2_2") (pintype "input"))
      (node (ref "R34") (pin "2") (pinfunction "2_2") (pintype "input"))
      (node (ref "U1") (pin "3") (pinfunction "GND_3") (pintype "unspecified"))
      (node (ref "U10") (pin "3") (pinfunction "GND_3") (pintype "unspecified"))
      (node (ref "U11") (pin "3") (pinfunction "GND_3") (pintype "unspecified"))
      (node (ref "U12") (pin "1") (pinfunction "GND_1") (pintype "unspecified"))
      (node (ref "U13") (pin "10") (pinfunction "GND_10") (pintype "unspecified"))
      (node (ref "U13") (pin "11") (pinfunction "GND_11") (pintype "unspecified"))
      (node (ref "U13") (pin "12") (pinfunction "GND_12") (pintype "unspecified"))
      (node (ref "U13") (pin "13") (pinfunction "GND_13") (pintype "unspecified"))
      (node (ref "U13") (pin "6") (pinfunction "VSS_6") (pintype "unspecified"))
      (node (ref "U14") (pin "2") (pinfunction "2_2") (pintype "unspecified"))
      (node (ref "U2") (pin "5") (pinfunction "GND_5") (pintype "input"))
      (node (ref "U2") (pin "6") (pinfunction "GND_6") (pintype "input"))
      (node (ref "U2") (pin "7") (pinfunction "GND_7") (pintype "input"))
      (node (ref "U2") (pin "8") (pinfunction "GND_8") (pintype "input"))
      (node (ref "U3") (pin "3") (pinfunction "GND_3") (pintype "unspecified"))
      (node (ref "U4") (pin "1") (pinfunction "GND_1") (pintype "unspecified"))
      (node (ref "U5") (pin "3") (pinfunction "GND_3") (pintype "unspecified"))
      (node (ref "U6") (pin "13") (pinfunction "OE#_13") (pintype "unspecified"))
      (node (ref "U6") (pin "8") (pinfunction "GND_8") (pintype "unspecified"))
      (node (ref "U7") (pin "13") (pinfunction "OE#_13") (pintype "unspecified"))
      (node (ref "U7") (pin "8") (pinfunction "GND_8") (pintype "unspecified"))
      (node (ref "U8") (pin "1") (pinfunction "GND_1") (pintype "unspecified"))
      (node (ref "U8") (pin "15") (pinfunction "GND_15") (pintype "unspecified"))
      (node (ref "U8") (pin "38") (pinfunction "GND_38") (pintype "unspecified"))
      (node (ref "U8") (pin "39") (pinfunction "EP_39") (pintype "unspecified"))
      (node (ref "U9") (pin "3") (pinfunction "GND_3") (pintype "unspecified"))
    )
    (net (code "69") (name "I2S_MR#") (class "Default")
      (node (ref "C19") (pin "2") (pinfunction "2_2") (pintype "unspecified"))
      (node (ref "R24") (pin "1") (pinfunction "1_1") (pintype "input"))
      (node (ref "U6") (pin "10") (pinfunction "MR#_10") (pintype "unspecified"))
      (node (ref "U7") (pin "10") (pinfunction "MR#_10") (pintype "unspecified"))
    )
    (net (code "70") (name "Net-(C17-Pad2)") (class "Default")
      (node (ref "C17") (pin "2") (pinfunction "2_2") (pintype "unspecified"))
      (node (ref "K1") (pin "3") (pinfunction "3_3") (pintype "unspecified"))
      (node (ref "K1") (pin "4") (pinfunction "4_4") (pintype "unspecified"))
      (node (ref "P14") (pin "1") (pintype "input"))
      (node (ref "R20") (pin "2") (pinfunction "2_2") (pintype "unspecified"))
      (node (ref "R25") (pin "2") (pinfunction "2_2") (pintype "input"))
    )
    (net (code "71") (name "Net-(C18-Pad2)") (class "Default")
      (node (ref "C18") (pin "2") (pinfunction "2_2") (pintype "unspecified"))
      (node (ref "P15") (pin "1") (pintype "input"))
      (node (ref "R21") (pin "2") (pinfunction "2_2") (pintype "unspecified"))
      (node (ref "R26") (pin "2") (pinfunction "2_2") (pintype "input"))
    )
    (net (code "72") (name "Net-(D3-Pad1)") (class "Default")
      (node (ref "D3") (pin "1") (pinfunction "1_1") (pintype "unspecified"))
      (node (ref "R7") (pin "1") (pinfunction "1_1") (pintype "unspecified"))
    )
    (net (code "73") (name "Net-(D5-Pad1)") (class "Default")
      (node (ref "D5") (pin "1") (pinfunction "1_1") (pintype "unspecified"))
      (node (ref "R9") (pin "1") (pinfunction "1_1") (pintype "unspecified"))
    )
    (net (code "74") (name "Net-(D7-Pad1)") (class "Default")
      (node (ref "D7") (pin "1") (pinfunction "1_1") (pintype "unspecified"))
      (node (ref "R14") (pin "1") (pinfunction "1_1") (pintype "unspecified"))
    )
    (net (code "75") (name "Net-(H1-Pad3)") (class "Default")
      (node (ref "H1") (pin "3") (pinfunction "3_3") (pintype "unspecified"))
      (node (ref "H1") (pin "4") (pinfunction "4_4") (pintype "unspecified"))
    )
    (net (code "76") (name "Net-(Q1-B)") (class "Default")
      (node (ref "Q1") (pin "1") (pinfunction "B_1") (pintype "input"))
      (node (ref "R33") (pin "1") (pinfunction "1_1") (pintype "input"))
      (node (ref "R35") (pin "2") (pinfunction "2_2") (pintype "input"))
    )
    (net (code "77") (name "Net-(Q2-B)") (class "Default")
      (node (ref "Q2") (pin "1") (pinfunction "B_1") (pintype "unspecified"))
      (node (ref "R41") (pin "2") (pinfunction "2_2") (pintype "unspecified"))
    )
    (net (code "78") (name "Net-(Q2-E)") (class "Default")
      (node (ref "Q2") (pin "2") (pinfunction "E_2") (pintype "unspecified"))
      (node (ref "R45") (pin "1") (pinfunction "1_1") (pintype "unspecified"))
      (node (ref "U12") (pin "13") (pinfunction "DTR#_13") (pintype "unspecified"))
    )
    (net (code "79") (name "Net-(Q3-B)") (class "Default")
      (node (ref "Q3") (pin "1") (pinfunction "B_1") (pintype "unspecified"))
      (node (ref "R45") (pin "2") (pinfunction "2_2") (pintype "unspecified"))
    )
    (net (code "80") (name "Net-(Q3-E)") (class "Default")
      (node (ref "Q3") (pin "2") (pinfunction "E_2") (pintype "unspecified"))
      (node (ref "R41") (pin "1") (pinfunction "1_1") (pintype "unspecified"))
      (node (ref "U12") (pin "14") (pinfunction "RTS#_14") (pintype "unspecified"))
    )
    (net (code "81") (name "Net-(U2-ON{slash}OFF)") (class "Default")
      (node (ref "R10") (pin "1") (pinfunction "1_1") (pintype "unspecified"))
      (node (ref "U2") (pin "4") (pinfunction "ON/OFF_4") (pintype "input"))
    )
    (net (code "82") (name "Net-(U2-OUTPUT)") (class "Default")
      (node (ref "D2") (pin "2") (pinfunction "2_2") (pintype "input"))
      (node (ref "L1") (pin "2") (pinfunction "2_2") (pintype "unspecified"))
      (node (ref "U2") (pin "2") (pinfunction "OUTPUT_2") (pintype "input"))
    )
    (net (code "83") (name "Net-(U6-Q7S)") (class "Default")
      (node (ref "U6") (pin "9") (pinfunction "Q7S_9") (pintype "unspecified"))
      (node (ref "U7") (pin "14") (pinfunction "DS_14") (pintype "unspecified"))
    )
    (net (code "84") (name "Net-(U12-RXD)") (class "Default")
      (node (ref "R38") (pin "2") (pinfunction "2_2") (pintype "input"))
      (node (ref "R39") (pin "1") (pinfunction "1_1") (pintype "unspecified"))
      (node (ref "U12") (pin "3") (pinfunction "RXD_3") (pintype "unspecified"))
    )
    (net (code "85") (name "Net-(U12-TXD)") (class "Default")
      (node (ref "R37") (pin "2") (pinfunction "2_2") (pintype "input"))
      (node (ref "U12") (pin "2") (pinfunction "TXD_2") (pintype "unspecified"))
    )
    (net (code "86") (name "Net-(U12-UD+)") (class "Default")
      (node (ref "U12") (pin "5") (pinfunction "UD+_5") (pintype "unspecified"))
      (node (ref "U14") (pin "6") (pinfunction "6_6") (pintype "unspecified"))
    )
    (net (code "87") (name "Net-(U12-UD-)") (class "Default")
      (node (ref "U12") (pin "6") (pinfunction "UD-_6") (pintype "unspecified"))
      (node (ref "U14") (pin "4") (pinfunction "4_4") (pintype "unspecified"))
    )
    (net (code "88") (name "Net-(U12-V3)") (class "Default")
      (node (ref "C25") (pin "1") (pinfunction "1_1") (pintype "unspecified"))
      (node (ref "U12") (pin "4") (pinfunction "V3_4") (pintype "unspecified"))
    )
    (net (code "89") (name "Net-(U12-XI)") (class "Default")
      (node (ref "C26") (pin "1") (pinfunction "1_1") (pintype "unspecified"))
      (node (ref "U12") (pin "7") (pinfunction "XI_7") (pintype "unspecified"))
      (node (ref "Y1") (pin "2") (pinfunction "OSC2_2") (pintype "unspecified"))
    )
    (net (code "90") (name "Net-(U12-XO)") (class "Default")
      (node (ref "C29") (pin "1") (pinfunction "1_1") (pintype "unspecified"))
      (node (ref "U12") (pin "8") (pinfunction "XO_8") (pintype "unspecified"))
      (node (ref "Y1") (pin "1") (pinfunction "OSC1_1") (pintype "unspecified"))
    )
    (net (code "91") (name "VIN_24V") (class "Default")
      (node (ref "C4") (pin "1") (pintype "unspecified"))
      (node (ref "C5") (pin "2") (pinfunction "2_2") (pintype "unspecified"))
      (node (ref "D1") (pin "2") (pinfunction "2_2") (pintype "unspecified"))
      (node (ref "U2") (pin "1") (pinfunction "VIN_1") (pintype "input"))
    )
    (net (code "92") (name "VUSB") (class "Default")
      (node (ref "H5") (pin "2") (pinfunction "2_2") (pintype "unspecified"))
      (node (ref "P18") (pin "1") (pinfunction "VBUS_1") (pintype "unspecified"))
      (node (ref "U14") (pin "5") (pinfunction "5_5") (pintype "unspecified"))
    )
    (net (code "93") (name "unconnected-(D10-GND-Pad2)") (class "Default")
      (node (ref "D10") (pin "2") (pinfunction "GND_2") (pintype "unspecified"))
    )
    (net (code "94") (name "unconnected-(D10-I{slash}O1-Pad1)") (class "Default")
      (node (ref "D10") (pin "1") (pinfunction "I/O1_1") (pintype "unspecified"))
    )
    (net (code "95") (name "unconnected-(D10-I{slash}O1-Pad6)") (class "Default")
      (node (ref "D10") (pin "6") (pinfunction "I/O1_6") (pintype "unspecified"))
    )
    (net (code "96") (name "unconnected-(D10-I{slash}O2-Pad3)") (class "Default")
      (node (ref "D10") (pin "3") (pinfunction "I/O2_3") (pintype "unspecified"))
    )
    (net (code "97") (name "unconnected-(D10-I{slash}O2-Pad4)") (class "Default")
      (node (ref "D10") (pin "4") (pinfunction "I/O2_4") (pintype "unspecified"))
    )
    (net (code "98") (name "unconnected-(D10-VBUS-Pad5)") (class "Default")
      (node (ref "D10") (pin "5") (pinfunction "VBUS_5") (pintype "unspecified"))
    )
    (net (code "99") (name "unconnected-(U3-NC-Pad1)") (class "Default")
      (node (ref "U3") (pin "1") (pinfunction "NC_1") (pintype "unspecified"))
    )
    (net (code "100") (name "unconnected-(U5-NC-Pad1)") (class "Default")
      (node (ref "U5") (pin "1") (pinfunction "NC_1") (pintype "unspecified"))
    )
    (net (code "101") (name "unconnected-(U7-Q5-Pad5)") (class "Default")
      (node (ref "U7") (pin "5") (pinfunction "Q5_5") (pintype "unspecified"))
    )
    (net (code "102") (name "unconnected-(U7-Q6-Pad6)") (class "Default")
      (node (ref "U7") (pin "6") (pinfunction "Q6_6") (pintype "unspecified"))
    )
    (net (code "103") (name "unconnected-(U7-Q7-Pad7)") (class "Default")
      (node (ref "U7") (pin "7") (pinfunction "Q7_7") (pintype "unspecified"))
    )
    (net (code "104") (name "unconnected-(U7-Q7S-Pad9)") (class "Default")
      (node (ref "U7") (pin "9") (pinfunction "Q7S_9") (pintype "unspecified"))
    )
    (net (code "105") (name "unconnected-(U8-CLK-Pad20)") (class "Default")
      (node (ref "U8") (pin "20") (pinfunction "CLK_20") (pintype "unspecified"))
    )
    (net (code "106") (name "unconnected-(U8-CMD-Pad19)") (class "Default")
      (node (ref "U8") (pin "19") (pinfunction "CMD_19") (pintype "unspecified"))
    )
    (net (code "107") (name "unconnected-(U8-NC-Pad32)") (class "Default")
      (node (ref "U8") (pin "32") (pinfunction "NC_32") (pintype "unspecified"))
    )
    (net (code "108") (name "unconnected-(U8-SD0-Pad21)") (class "Default")
      (node (ref "U8") (pin "21") (pinfunction "SD0_21") (pintype "unspecified"))
    )
    (net (code "109") (name "unconnected-(U8-SD1-Pad22)") (class "Default")
      (node (ref "U8") (pin "22") (pinfunction "SD1_22") (pintype "unspecified"))
    )
    (net (code "110") (name "unconnected-(U8-SD2-Pad17)") (class "Default")
      (node (ref "U8") (pin "17") (pinfunction "SD2_17") (pintype "unspecified"))
    )
    (net (code "111") (name "unconnected-(U8-SD3-Pad18)") (class "Default")
      (node (ref "U8") (pin "18") (pinfunction "SD3_18") (pintype "unspecified"))
    )
    (net (code "112") (name "unconnected-(U9-NC-Pad1)") (class "Default")
      (node (ref "U9") (pin "1") (pinfunction "NC_1") (pintype "unspecified"))
    )
    (net (code "113") (name "unconnected-(U10-NC-Pad1)") (class "Default")
      (node (ref "U10") (pin "1") (pinfunction "NC_1") (pintype "unspecified"))
    )
    (net (code "114") (name "unconnected-(U11-NC-Pad1)") (class "Default")
      (node (ref "U11") (pin "1") (pinfunction "NC_1") (pintype "unspecified"))
    )
    (net (code "115") (name "unconnected-(U12-CTS#-Pad9)") (class "Default")
      (node (ref "U12") (pin "9") (pinfunction "CTS#_9") (pintype "unspecified"))
    )
    (net (code "116") (name "unconnected-(U12-DCD#-Pad12)") (class "Default")
      (node (ref "U12") (pin "12") (pinfunction "DCD#_12") (pintype "unspecified"))
    )
    (net (code "117") (name "unconnected-(U12-DSR#-Pad10)") (class "Default")
      (node (ref "U12") (pin "10") (pinfunction "DSR#_10") (pintype "unspecified"))
    )
    (net (code "118") (name "unconnected-(U12-R232-Pad15)") (class "Default")
      (node (ref "U12") (pin "15") (pinfunction "R232_15") (pintype "unspecified"))
    )
    (net (code "119") (name "unconnected-(U12-RI#-Pad11)") (class "Default")
      (node (ref "U12") (pin "11") (pinfunction "RI#_11") (pintype "unspecified"))
    )
    (net (code "120") (name "unconnected-(U13-DAT1-Pad8)") (class "Default")
      (node (ref "U13") (pin "8") (pinfunction "DAT1_8") (pintype "unspecified"))
    )
    (net (code "121") (name "unconnected-(U13-DAT2-Pad1)") (class "Default")
      (node (ref "U13") (pin "1") (pinfunction "DAT2_1") (pintype "unspecified"))
    )
  )
)
